# EN_Probe_VR_Chain_BD1.net
KiCad netlist of a schematic drawn in Altium Designer
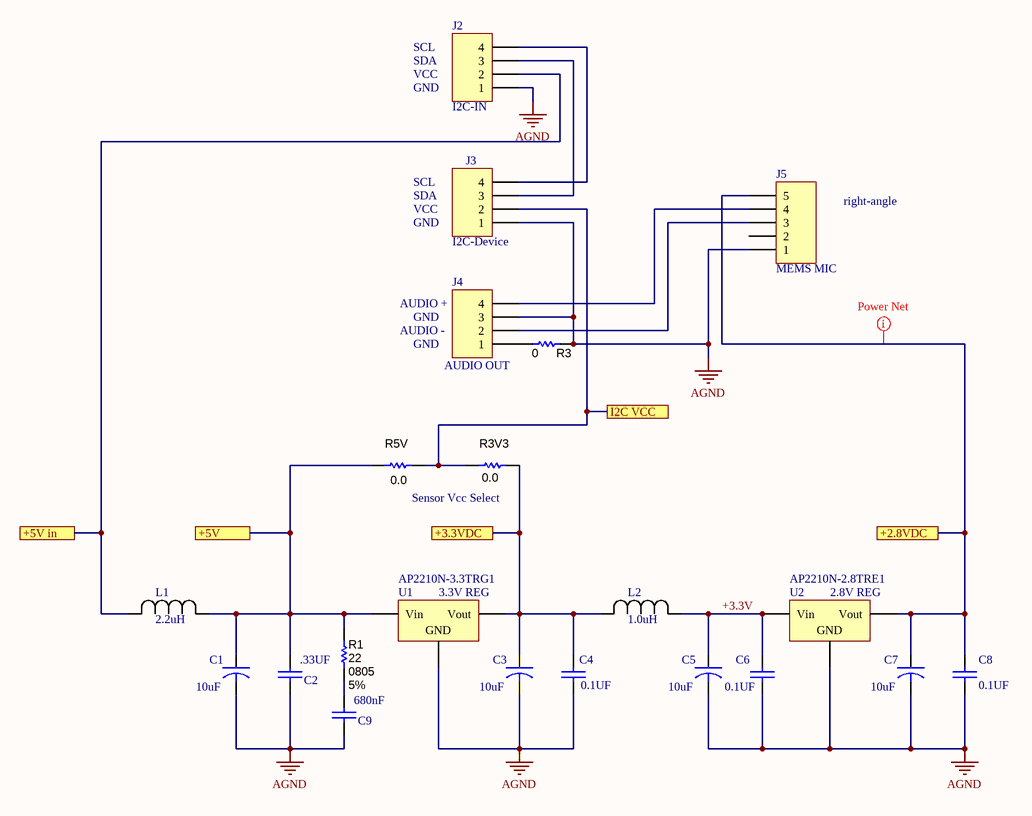
[diagram p0: EN_Probe_VR_Chain_BD1.SchDoc]

(export (version "E")
  (design (tool "Eeschema 10.0.6"))
  (components
    (comp (ref "C1")
      (value "10uF")
      (footprint "0805")
      (description "CAP CER 10UF 25V X5R 0805")
      (libsource (lib "*") (part "CAPACITOR"))
    )
    (comp (ref "C2")
      (value ".33UF")
      (footprint "0805")
      (description "CAP CER 0.33UF 25V X7R 0805")
      (libsource (lib "*") (part "CAP"))
    )
    (comp (ref "C3")
      (value "10uF")
      (footprint "0805")
      (description "CAP CER 10UF 25V X5R 0805")
      (libsource (lib "*") (part "CAPACITOR"))
    )
    (comp (ref "C4")
      (value "0.1UF")
      (footprint "0603")
      (description "CAP CER 0.1UF 50V X7R 0603")
      (libsource (lib "*") (part "CAP"))
    )
    (comp (ref "C5")
      (value "10uF")
      (footprint "0805")
      (description "CAP CER 10UF 25V X5R 0805")
      (libsource (lib "*") (part "CAPACITOR"))
    )
    (comp (ref "C6")
      (value "0.1UF")
      (footprint "0603")
      (description "CAP CER 0.1UF 50V X7R 0603")
      (libsource (lib "*") (part "CAP"))
    )
    (comp (ref "C7")
      (value "10uF")
      (footprint "0805")
      (description "CAP CER 10UF 25V X5R 0805")
      (libsource (lib "*") (part "CAPACITOR"))
    )
    (comp (ref "C8")
      (value "0.1UF")
      (footprint "0603")
      (description "CAP CER 0.1UF 50V X7R 0603")
      (libsource (lib "*") (part "CAP"))
    )
    (comp (ref "C9")
      (value "680nF")
      (footprint "0805")
      (description "CAP CER 0.33UF 25V X7R 0805")
      (libsource (lib "*") (part "CAP"))
    )
    (comp (ref "J2")
      (value "I2C-IN")
      (footprint "HDRA1X4 2MM")
      (description "CONN HEADER VERT 4POS .100 TIN")
      (fields
        (field (name "MANUFACTURER") "TE Connectivity AMP Connectors")
        (field (name "PUBLISHER") "Altium Limited")
      )
      (libsource (lib "Miscellaneous Connectors") (part "Header 4"))
    )
    (comp (ref "J3")
      (value "I2C-Device")
      (footprint "HDRA1X4 2MM")
      (description "CONN HEADER VERT 4POS .100 TIN")
      (fields
        (field (name "MANUFACTURER") "TE Connectivity AMP Connectors")
        (field (name "PUBLISHER") "Altium Limited")
      )
      (libsource (lib "Miscellaneous Connectors") (part "Header 4"))
    )
    (comp (ref "J4")
      (value "AUDIO OUT")
      (footprint "HDRA1X4 2MM")
      (description "CONN HEADER VERT 4POS .100 TIN")
      (fields
        (field (name "MANUFACTURER") "TE Connectivity AMP Connectors")
        (field (name "PUBLISHER") "Altium Limited")
      )
      (libsource (lib "Miscellaneous Connectors") (part "Header 4"))
    )
    (comp (ref "J5")
      (value "MEMS MIC")
      (footprint "HDR1X5")
      (description "CONN HEADER VERT 5POS 2.54MM")
      (fields (field (name "MANUFACTURER") "Harwin Inc."))
      (libsource (lib "altium") (part "CONN1X5"))
    )
    (comp (ref "L1")
      (value "2.2uH")
      (footprint "1206")
      (description "FERRITE BEAD 160 OHM 1206 1LN")
      (fields
        (field (name "MANUFACTURER_PART_NUMBER") "HI1206T161R-10")
        (field (name "COPYRIGHT") "Copyright (C) 2018 Accelerated Designs. All rights reserved")
      )
      (libsource (lib "2020-08-13_00-23-02") (part "HI1206T161R-10"))
    )
    (comp (ref "L2")
      (value "1.0uH")
      (footprint "1206")
      (description "FERRITE BEAD 160 OHM 1206 1LN")
      (fields
        (field (name "MANUFACTURER_PART_NUMBER") "HI1206T161R-10")
        (field (name "COPYRIGHT") "Copyright (C) 2018 Accelerated Designs. All rights reserved")
      )
      (libsource (lib "2020-08-13_00-23-02") (part "HI1206T161R-10"))
    )
    (comp (ref "R1")
      (value "CRCW080522R0JNEA")
      (footprint "0805")
      (description "RES, 22, 5%, 0.125 W, 0805")
      (fields
        (field (name "MANUFACTURER") "Vishay-Dale")
        (field (name "VALUEDISPLAYED") "22")
        (field (name "PACKAGEREFERENCE") "0805")
        (field (name "VALUE1") "5%")
        (field (name "PUBLISHER") "Texas Instruments")
      )
      (libsource (lib "SugarCube SCADng_R3.1 40") (part "CRCW080522R0JNEA"))
    )
    (comp (ref "R3")
      (value "CRCW080522R0JNEA")
      (footprint "0805")
      (description "RES, 22, 5%, 0.125 W, 0805")
      (fields
        (field (name "MANUFACTURER") "Vishay-Dale")
        (field (name "VALUEDISPLAYED") "0")
        (field (name "PUBLISHER") "Texas Instruments")
      )
      (libsource (lib "SugarCube SCADng_R3.1 40") (part "CRCW080522R0JNEA"))
    )
    (comp (ref "R3V3")
      (value "CRCW080522R0JNEA")
      (footprint "0805")
      (description "RES, 22, 5%, 0.125 W, 0805")
      (fields
        (field (name "MANUFACTURER") "Vishay-Dale")
        (field (name "VALUEDISPLAYED") "0.0")
        (field (name "PUBLISHER") "Texas Instruments")
      )
      (libsource (lib "SugarCube SCADng_R3.1 40") (part "CRCW080522R0JNEA"))
    )
    (comp (ref "R5V")
      (value "CRCW080522R0JNEA")
      (footprint "0805")
      (description "RES, 22, 5%, 0.125 W, 0805")
      (fields
        (field (name "MANUFACTURER") "Vishay-Dale")
        (field (name "VALUEDISPLAYED") "0.0")
        (field (name "PUBLISHER") "Texas Instruments")
      )
      (libsource (lib "SugarCube SCADng_R3.1 40") (part "CRCW080522R0JNEA"))
    )
    (comp (ref "U1")
      (value "3.3V REG")
      (footprint "SOT23-3")
      (description "IC REG LINEAR 3.3V 300MA SOT23-3")
      (fields (field (name "PUBLISHER") "Altium Limited"))
      (libsource (lib "EN_Probe_VR") (part "Volt Reg"))
    )
    (comp (ref "U2")
      (value "2.8V REG")
      (footprint "SOT23-3")
      (description "IC REG LINEAR 2.8V 300MA SOT23-3")
      (fields (field (name "PUBLISHER") "Altium Limited"))
      (libsource (lib "EN_Probe_VR") (part "Volt Reg"))
    )
  )
  (nets
    (net (code "1") (name "/+2.8VDC") (class "Default")
      (node (ref "C7") (pin "1") (pinfunction "1_1") (pintype "passive"))
      (node (ref "C8") (pin "2") (pintype "passive"))
      (node (ref "J5") (pin "5") (pinfunction "5_5") (pintype "passive"))
      (node (ref "U2") (pin "2") (pinfunction "Vout_2") (pintype "passive"))
    )
    (net (code "2") (name "/+3.3V") (class "Default")
      (node (ref "C5") (pin "1") (pinfunction "1_1") (pintype "passive"))
      (node (ref "C6") (pin "2") (pintype "passive"))
      (node (ref "L2") (pin "1") (pinfunction "1_1") (pintype "passive"))
      (node (ref "U2") (pin "3") (pinfunction "Vin_3") (pintype "passive"))
    )
    (net (code "3") (name "/+3.3VDC") (class "Default")
      (node (ref "C3") (pin "1") (pinfunction "1_1") (pintype "passive"))
      (node (ref "C4") (pin "1") (pintype "passive"))
      (node (ref "L2") (pin "2") (pinfunction "2_2") (pintype "passive"))
      (node (ref "R3V3") (pin "2") (pinfunction "2_2") (pintype "passive"))
      (node (ref "U1") (pin "2") (pinfunction "Vout_2") (pintype "passive"))
    )
    (net (code "4") (name "/+5V") (class "Default")
      (node (ref "C1") (pin "1") (pinfunction "1_1") (pintype "passive"))
      (node (ref "C2") (pin "2") (pintype "passive"))
      (node (ref "L1") (pin "1") (pinfunction "1_1") (pintype "passive"))
      (node (ref "R1") (pin "2") (pinfunction "2_2") (pintype "passive"))
      (node (ref "R5V") (pin "2") (pinfunction "2_2") (pintype "passive"))
      (node (ref "U1") (pin "3") (pinfunction "Vin_3") (pintype "passive"))
    )
    (net (code "5") (name "/+5V in") (class "Default")
      (node (ref "J2") (pin "2") (pinfunction "2_2") (pintype "passive"))
      (node (ref "L1") (pin "2") (pinfunction "2_2") (pintype "passive"))
    )
    (net (code "6") (name "/I2C VCC") (class "Default")
      (node (ref "J3") (pin "2") (pinfunction "2_2") (pintype "passive"))
      (node (ref "R3V3") (pin "1") (pinfunction "1_1") (pintype "passive"))
      (node (ref "R5V") (pin "1") (pinfunction "1_1") (pintype "passive"))
    )
    (net (code "7") (name "AGND") (class "Default")
      (node (ref "C1") (pin "2") (pinfunction "2_2") (pintype "passive"))
      (node (ref "C2") (pin "1") (pintype "passive"))
      (node (ref "C3") (pin "2") (pinfunction "2_2") (pintype "passive"))
      (node (ref "C4") (pin "2") (pintype "passive"))
      (node (ref "C5") (pin "2") (pinfunction "2_2") (pintype "passive"))
      (node (ref "C6") (pin "1") (pintype "passive"))
      (node (ref "C7") (pin "2") (pinfunction "2_2") (pintype "passive"))
      (node (ref "C8") (pin "1") (pintype "passive"))
      (node (ref "C9") (pin "1") (pintype "passive"))
      (node (ref "J2") (pin "1") (pinfunction "1_1") (pintype "passive"))
      (node (ref "J3") (pin "1") (pinfunction "1_1") (pintype "passive"))
      (node (ref "J4") (pin "3") (pinfunction "3_3") (pintype "passive"))
      (node (ref "J5") (pin "1") (pinfunction "1_1") (pintype "passive"))
      (node (ref "R3") (pin "1") (pinfunction "1_1") (pintype "passive"))
      (node (ref "U1") (pin "1") (pinfunction "GND_1") (pintype "passive"))
      (node (ref "U2") (pin "1") (pinfunction "GND_1") (pintype "passive"))
    )
    (net (code "8") (name "Net-(C9-Pad2)") (class "Default")
      (node (ref "C9") (pin "2") (pintype "passive"))
      (node (ref "R1") (pin "1") (pinfunction "1_1") (pintype "passive"))
    )
    (net (code "9") (name "Net-(J2-Pad3)") (class "Default")
      (node (ref "J2") (pin "3") (pinfunction "3_3") (pintype "passive"))
      (node (ref "J3") (pin "3") (pinfunction "3_3") (pintype "passive"))
    )
    (net (code "10") (name "Net-(J2-Pad4)") (class "Default")
      (node (ref "J2") (pin "4") (pinfunction "4_4") (pintype "passive"))
      (node (ref "J3") (pin "4") (pinfunction "4_4") (pintype "passive"))
    )
    (net (code "11") (name "Net-(J4-Pad1)") (class "Default")
      (node (ref "J4") (pin "1") (pinfunction "1_1") (pintype "passive"))
      (node (ref "R3") (pin "2") (pinfunction "2_2") (pintype "passive"))
    )
    (net (code "12") (name "Net-(J4-Pad2)") (class "Default")
      (node (ref "J4") (pin "2") (pinfunction "2_2") (pintype "passive"))
      (node (ref "J5") (pin "3") (pinfunction "3_3") (pintype "passive"))
    )
    (net (code "13") (name "Net-(J4-Pad4)") (class "Default")
      (node (ref "J4") (pin "4") (pinfunction "4_4") (pintype "passive"))
      (node (ref "J5") (pin "4") (pinfunction "4_4") (pintype "passive"))
    )
    (net (code "14") (name "unconnected-(J5-Pad2)") (class "Default")
      (node (ref "J5") (pin "2") (pinfunction "2_2") (pintype "passive"))
    )
  )
)
